# Charlieplex84.net
KiCad netlist of a schematic drawn in EAGLE
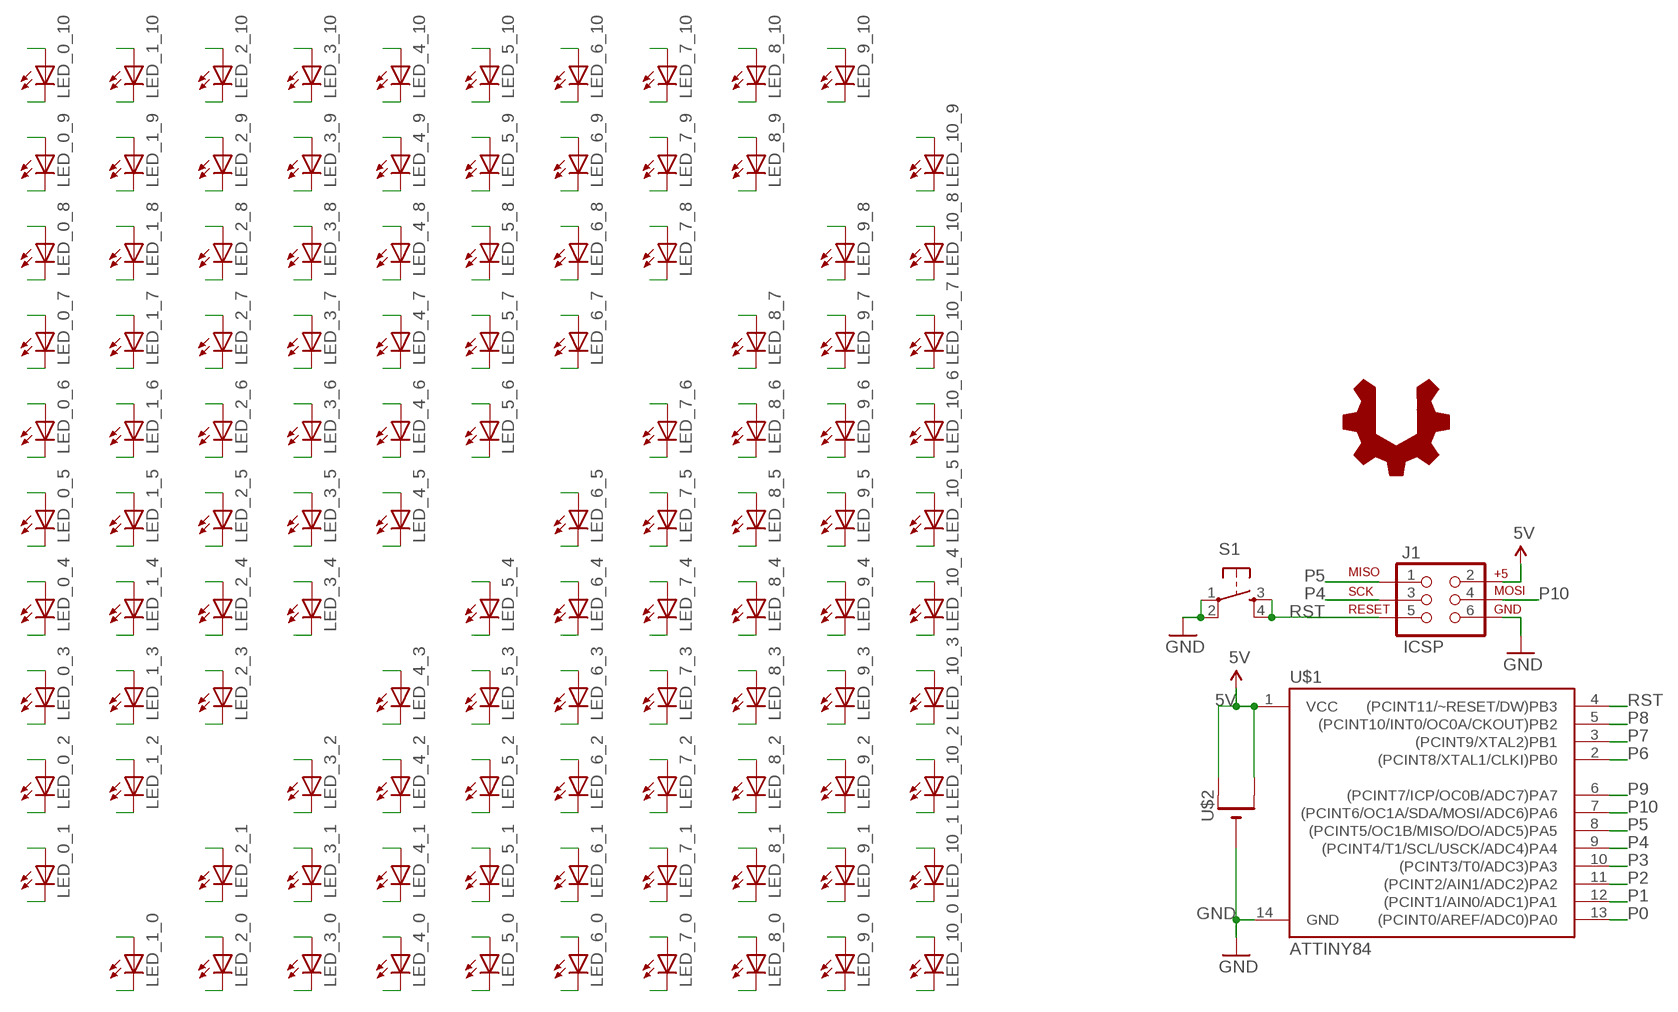
[diagram p0: schematic, sheet 1]

(export (version "E")
  (design (tool "Eeschema 10.0.6"))
  (components
    (comp (ref "J1")
      (value "ICSP")
      (footprint "eagle-import:2X3-NS")
      (libsource (lib "eagle-import") (part "AVR_SPI_PRG_6LABELED"))
    )
    (comp (ref "LED_0_1")
      (value "LEDOVAL")
      (footprint "eagle-import:LED-OVAL")
      (libsource (lib "eagle-import") (part "LEDOVAL"))
    )
    (comp (ref "LED_0_2")
      (value "LEDOVAL")
      (footprint "eagle-import:LED-OVAL")
      (libsource (lib "eagle-import") (part "LEDOVAL"))
    )
    (comp (ref "LED_0_3")
      (value "LEDOVAL")
      (footprint "eagle-import:LED-OVAL")
      (libsource (lib "eagle-import") (part "LEDOVAL"))
    )
    (comp (ref "LED_0_4")
      (value "LEDOVAL")
      (footprint "eagle-import:LED-OVAL")
      (libsource (lib "eagle-import") (part "LEDOVAL"))
    )
    (comp (ref "LED_0_5")
      (value "LEDOVAL")
      (footprint "eagle-import:LED-OVAL")
      (libsource (lib "eagle-import") (part "LEDOVAL"))
    )
    (comp (ref "LED_0_6")
      (value "LEDOVAL")
      (footprint "eagle-import:LED-OVAL")
      (libsource (lib "eagle-import") (part "LEDOVAL"))
    )
    (comp (ref "LED_0_7")
      (value "LEDOVAL")
      (footprint "eagle-import:LED-OVAL")
      (libsource (lib "eagle-import") (part "LEDOVAL"))
    )
    (comp (ref "LED_0_8")
      (value "LEDOVAL")
      (footprint "eagle-import:LED-OVAL")
      (libsource (lib "eagle-import") (part "LEDOVAL"))
    )
    (comp (ref "LED_0_9")
      (value "LEDOVAL")
      (footprint "eagle-import:LED-OVAL")
      (libsource (lib "eagle-import") (part "LEDOVAL"))
    )
    (comp (ref "LED_0_10")
      (value "LEDOVAL")
      (footprint "eagle-import:LED-OVAL")
      (libsource (lib "eagle-import") (part "LEDOVAL"))
    )
    (comp (ref "LED_1_0")
      (value "LEDOVAL")
      (footprint "eagle-import:LED-OVAL")
      (libsource (lib "eagle-import") (part "LEDOVAL"))
    )
    (comp (ref "LED_1_2")
      (value "LEDOVAL")
      (footprint "eagle-import:LED-OVAL")
      (libsource (lib "eagle-import") (part "LEDOVAL"))
    )
    (comp (ref "LED_1_3")
      (value "LEDOVAL")
      (footprint "eagle-import:LED-OVAL")
      (libsource (lib "eagle-import") (part "LEDOVAL"))
    )
    (comp (ref "LED_1_4")
      (value "LEDOVAL")
      (footprint "eagle-import:LED-OVAL")
      (libsource (lib "eagle-import") (part "LEDOVAL"))
    )
    (comp (ref "LED_1_5")
      (value "LEDOVAL")
      (footprint "eagle-import:LED-OVAL")
      (libsource (lib "eagle-import") (part "LEDOVAL"))
    )
    (comp (ref "LED_1_6")
      (value "LEDOVAL")
      (footprint "eagle-import:LED-OVAL")
      (libsource (lib "eagle-import") (part "LEDOVAL"))
    )
    (comp (ref "LED_1_7")
      (value "LEDOVAL")
      (footprint "eagle-import:LED-OVAL")
      (libsource (lib "eagle-import") (part "LEDOVAL"))
    )
    (comp (ref "LED_1_8")
      (value "LEDOVAL")
      (footprint "eagle-import:LED-OVAL")
      (libsource (lib "eagle-import") (part "LEDOVAL"))
    )
    (comp (ref "LED_1_9")
      (value "LEDOVAL")
      (footprint "eagle-import:LED-OVAL")
      (libsource (lib "eagle-import") (part "LEDOVAL"))
    )
    (comp (ref "LED_1_10")
      (value "LEDOVAL")
      (footprint "eagle-import:LED-OVAL")
      (libsource (lib "eagle-import") (part "LEDOVAL"))
    )
    (comp (ref "LED_2_0")
      (value "LEDOVAL")
      (footprint "eagle-import:LED-OVAL")
      (libsource (lib "eagle-import") (part "LEDOVAL"))
    )
    (comp (ref "LED_2_1")
      (value "LEDOVAL")
      (footprint "eagle-import:LED-OVAL")
      (libsource (lib "eagle-import") (part "LEDOVAL"))
    )
    (comp (ref "LED_2_3")
      (value "LEDOVAL")
      (footprint "eagle-import:LED-OVAL")
      (libsource (lib "eagle-import") (part "LEDOVAL"))
    )
    (comp (ref "LED_2_4")
      (value "LEDOVAL")
      (footprint "eagle-import:LED-OVAL")
      (libsource (lib "eagle-import") (part "LEDOVAL"))
    )
    (comp (ref "LED_2_5")
      (value "LEDOVAL")
      (footprint "eagle-import:LED-OVAL")
      (libsource (lib "eagle-import") (part "LEDOVAL"))
    )
    (comp (ref "LED_2_6")
      (value "LEDOVAL")
      (footprint "eagle-import:LED-OVAL")
      (libsource (lib "eagle-import") (part "LEDOVAL"))
    )
    (comp (ref "LED_2_7")
      (value "LEDOVAL")
      (footprint "eagle-import:LED-OVAL")
      (libsource (lib "eagle-import") (part "LEDOVAL"))
    )
    (comp (ref "LED_2_8")
      (value "LEDOVAL")
      (footprint "eagle-import:LED-OVAL")
      (libsource (lib "eagle-import") (part "LEDOVAL"))
    )
    (comp (ref "LED_2_9")
      (value "LEDOVAL")
      (footprint "eagle-import:LED-OVAL")
      (libsource (lib "eagle-import") (part "LEDOVAL"))
    )
    (comp (ref "LED_2_10")
      (value "LEDOVAL")
      (footprint "eagle-import:LED-OVAL")
      (libsource (lib "eagle-import") (part "LEDOVAL"))
    )
    (comp (ref "LED_3_0")
      (value "LEDOVAL")
      (footprint "eagle-import:LED-OVAL")
      (libsource (lib "eagle-import") (part "LEDOVAL"))
    )
    (comp (ref "LED_3_1")
      (value "LEDOVAL")
      (footprint "eagle-import:LED-OVAL")
      (libsource (lib "eagle-import") (part "LEDOVAL"))
    )
    (comp (ref "LED_3_2")
      (value "LEDOVAL")
      (footprint "eagle-import:LED-OVAL")
      (libsource (lib "eagle-import") (part "LEDOVAL"))
    )
    (comp (ref "LED_3_4")
      (value "LEDOVAL")
      (footprint "eagle-import:LED-OVAL")
      (libsource (lib "eagle-import") (part "LEDOVAL"))
    )
    (comp (ref "LED_3_5")
      (value "LEDOVAL")
      (footprint "eagle-import:LED-OVAL")
      (libsource (lib "eagle-import") (part "LEDOVAL"))
    )
    (comp (ref "LED_3_6")
      (value "LEDOVAL")
      (footprint "eagle-import:LED-OVAL")
      (libsource (lib "eagle-import") (part "LEDOVAL"))
    )
    (comp (ref "LED_3_7")
      (value "LEDOVAL")
      (footprint "eagle-import:LED-OVAL")
      (libsource (lib "eagle-import") (part "LEDOVAL"))
    )
    (comp (ref "LED_3_8")
      (value "LEDOVAL")
      (footprint "eagle-import:LED-OVAL")
      (libsource (lib "eagle-import") (part "LEDOVAL"))
    )
    (comp (ref "LED_3_9")
      (value "LEDOVAL")
      (footprint "eagle-import:LED-OVAL")
      (libsource (lib "eagle-import") (part "LEDOVAL"))
    )
    (comp (ref "LED_3_10")
      (value "LEDOVAL")
      (footprint "eagle-import:LED-OVAL")
      (libsource (lib "eagle-import") (part "LEDOVAL"))
    )
    (comp (ref "LED_4_0")
      (value "LEDOVAL")
      (footprint "eagle-import:LED-OVAL")
      (libsource (lib "eagle-import") (part "LEDOVAL"))
    )
    (comp (ref "LED_4_1")
      (value "LEDOVAL")
      (footprint "eagle-import:LED-OVAL")
      (libsource (lib "eagle-import") (part "LEDOVAL"))
    )
    (comp (ref "LED_4_2")
      (value "LEDOVAL")
      (footprint "eagle-import:LED-OVAL")
      (libsource (lib "eagle-import") (part "LEDOVAL"))
    )
    (comp (ref "LED_4_3")
      (value "LEDOVAL")
      (footprint "eagle-import:LED-OVAL")
      (libsource (lib "eagle-import") (part "LEDOVAL"))
    )
    (comp (ref "LED_4_5")
      (value "LEDOVAL")
      (footprint "eagle-import:LED-OVAL")
      (libsource (lib "eagle-import") (part "LEDOVAL"))
    )
    (comp (ref "LED_4_6")
      (value "LEDOVAL")
      (footprint "eagle-import:LED-OVAL")
      (libsource (lib "eagle-import") (part "LEDOVAL"))
    )
    (comp (ref "LED_4_7")
      (value "LEDOVAL")
      (footprint "eagle-import:LED-OVAL")
      (libsource (lib "eagle-import") (part "LEDOVAL"))
    )
    (comp (ref "LED_4_8")
      (value "LEDOVAL")
      (footprint "eagle-import:LED-OVAL")
      (libsource (lib "eagle-import") (part "LEDOVAL"))
    )
    (comp (ref "LED_4_9")
      (value "LEDOVAL")
      (footprint "eagle-import:LED-OVAL")
      (libsource (lib "eagle-import") (part "LEDOVAL"))
    )
    (comp (ref "LED_4_10")
      (value "LEDOVAL")
      (footprint "eagle-import:LED-OVAL")
      (libsource (lib "eagle-import") (part "LEDOVAL"))
    )
    (comp (ref "LED_5_0")
      (value "LEDOVAL")
      (footprint "eagle-import:LED-OVAL")
      (libsource (lib "eagle-import") (part "LEDOVAL"))
    )
    (comp (ref "LED_5_1")
      (value "LEDOVAL")
      (footprint "eagle-import:LED-OVAL")
      (libsource (lib "eagle-import") (part "LEDOVAL"))
    )
    (comp (ref "LED_5_2")
      (value "LEDOVAL")
      (footprint "eagle-import:LED-OVAL")
      (libsource (lib "eagle-import") (part "LEDOVAL"))
    )
    (comp (ref "LED_5_3")
      (value "LEDOVAL")
      (footprint "eagle-import:LED-OVAL")
      (libsource (lib "eagle-import") (part "LEDOVAL"))
    )
    (comp (ref "LED_5_4")
      (value "LEDOVAL")
      (footprint "eagle-import:LED-OVAL")
      (libsource (lib "eagle-import") (part "LEDOVAL"))
    )
    (comp (ref "LED_5_6")
      (value "LEDOVAL")
      (footprint "eagle-import:LED-OVAL")
      (libsource (lib "eagle-import") (part "LEDOVAL"))
    )
    (comp (ref "LED_5_7")
      (value "LEDOVAL")
      (footprint "eagle-import:LED-OVAL")
      (libsource (lib "eagle-import") (part "LEDOVAL"))
    )
    (comp (ref "LED_5_8")
      (value "LEDOVAL")
      (footprint "eagle-import:LED-OVAL")
      (libsource (lib "eagle-import") (part "LEDOVAL"))
    )
    (comp (ref "LED_5_9")
      (value "LEDOVAL")
      (footprint "eagle-import:LED-OVAL")
      (libsource (lib "eagle-import") (part "LEDOVAL"))
    )
    (comp (ref "LED_5_10")
      (value "LEDOVAL")
      (footprint "eagle-import:LED-OVAL")
      (libsource (lib "eagle-import") (part "LEDOVAL"))
    )
    (comp (ref "LED_6_0")
      (value "LEDOVAL")
      (footprint "eagle-import:LED-OVAL")
      (libsource (lib "eagle-import") (part "LEDOVAL"))
    )
    (comp (ref "LED_6_1")
      (value "LEDOVAL")
      (footprint "eagle-import:LED-OVAL")
      (libsource (lib "eagle-import") (part "LEDOVAL"))
    )
    (comp (ref "LED_6_2")
      (value "LEDOVAL")
      (footprint "eagle-import:LED-OVAL")
      (libsource (lib "eagle-import") (part "LEDOVAL"))
    )
    (comp (ref "LED_6_3")
      (value "LEDOVAL")
      (footprint "eagle-import:LED-OVAL")
      (libsource (lib "eagle-import") (part "LEDOVAL"))
    )
    (comp (ref "LED_6_4")
      (value "LEDOVAL")
      (footprint "eagle-import:LED-OVAL")
      (libsource (lib "eagle-import") (part "LEDOVAL"))
    )
    (comp (ref "LED_6_5")
      (value "LEDOVAL")
      (footprint "eagle-import:LED-OVAL")
      (libsource (lib "eagle-import") (part "LEDOVAL"))
    )
    (comp (ref "LED_6_7")
      (value "LEDOVAL")
      (footprint "eagle-import:LED-OVAL")
      (libsource (lib "eagle-import") (part "LEDOVAL"))
    )
    (comp (ref "LED_6_8")
      (value "LEDOVAL")
      (footprint "eagle-import:LED-OVAL")
      (libsource (lib "eagle-import") (part "LEDOVAL"))
    )
    (comp (ref "LED_6_9")
      (value "LEDOVAL")
      (footprint "eagle-import:LED-OVAL")
      (libsource (lib "eagle-import") (part "LEDOVAL"))
    )
    (comp (ref "LED_6_10")
      (value "LEDOVAL")
      (footprint "eagle-import:LED-OVAL")
      (libsource (lib "eagle-import") (part "LEDOVAL"))
    )
    (comp (ref "LED_7_0")
      (value "LEDOVAL")
      (footprint "eagle-import:LED-OVAL")
      (libsource (lib "eagle-import") (part "LEDOVAL"))
    )
    (comp (ref "LED_7_1")
      (value "LEDOVAL")
      (footprint "eagle-import:LED-OVAL")
      (libsource (lib "eagle-import") (part "LEDOVAL"))
    )
    (comp (ref "LED_7_2")
      (value "LEDOVAL")
      (footprint "eagle-import:LED-OVAL")
      (libsource (lib "eagle-import") (part "LEDOVAL"))
    )
    (comp (ref "LED_7_3")
      (value "LEDOVAL")
      (footprint "eagle-import:LED-OVAL")
      (libsource (lib "eagle-import") (part "LEDOVAL"))
    )
    (comp (ref "LED_7_4")
      (value "LEDOVAL")
      (footprint "eagle-import:LED-OVAL")
      (libsource (lib "eagle-import") (part "LEDOVAL"))
    )
    (comp (ref "LED_7_5")
      (value "LEDOVAL")
      (footprint "eagle-import:LED-OVAL")
      (libsource (lib "eagle-import") (part "LEDOVAL"))
    )
    (comp (ref "LED_7_6")
      (value "LEDOVAL")
      (footprint "eagle-import:LED-OVAL")
      (libsource (lib "eagle-import") (part "LEDOVAL"))
    )
    (comp (ref "LED_7_8")
      (value "LEDOVAL")
      (footprint "eagle-import:LED-OVAL")
      (libsource (lib "eagle-import") (part "LEDOVAL"))
    )
    (comp (ref "LED_7_9")
      (value "LEDOVAL")
      (footprint "eagle-import:LED-OVAL")
      (libsource (lib "eagle-import") (part "LEDOVAL"))
    )
    (comp (ref "LED_7_10")
      (value "LEDOVAL")
      (footprint "eagle-import:LED-OVAL")
      (libsource (lib "eagle-import") (part "LEDOVAL"))
    )
    (comp (ref "LED_8_0")
      (value "LEDOVAL")
      (footprint "eagle-import:LED-OVAL")
      (libsource (lib "eagle-import") (part "LEDOVAL"))
    )
    (comp (ref "LED_8_1")
      (value "LEDOVAL")
      (footprint "eagle-import:LED-OVAL")
      (libsource (lib "eagle-import") (part "LEDOVAL"))
    )
    (comp (ref "LED_8_2")
      (value "LEDOVAL")
      (footprint "eagle-import:LED-OVAL")
      (libsource (lib "eagle-import") (part "LEDOVAL"))
    )
    (comp (ref "LED_8_3")
      (value "LEDOVAL")
      (footprint "eagle-import:LED-OVAL")
      (libsource (lib "eagle-import") (part "LEDOVAL"))
    )
    (comp (ref "LED_8_4")
      (value "LEDOVAL")
      (footprint "eagle-import:LED-OVAL")
      (libsource (lib "eagle-import") (part "LEDOVAL"))
    )
    (comp (ref "LED_8_5")
      (value "LEDOVAL")
      (footprint "eagle-import:LED-OVAL")
      (libsource (lib "eagle-import") (part "LEDOVAL"))
    )
    (comp (ref "LED_8_6")
      (value "LEDOVAL")
      (footprint "eagle-import:LED-OVAL")
      (libsource (lib "eagle-import") (part "LEDOVAL"))
    )
    (comp (ref "LED_8_7")
      (value "LEDOVAL")
      (footprint "eagle-import:LED-OVAL")
      (libsource (lib "eagle-import") (part "LEDOVAL"))
    )
    (comp (ref "LED_8_9")
      (value "LEDOVAL")
      (footprint "eagle-import:LED-OVAL")
      (libsource (lib "eagle-import") (part "LEDOVAL"))
    )
    (comp (ref "LED_8_10")
      (value "LEDOVAL")
      (footprint "eagle-import:LED-OVAL")
      (libsource (lib "eagle-import") (part "LEDOVAL"))
    )
    (comp (ref "LED_9_0")
      (value "LEDOVAL")
      (footprint "eagle-import:LED-OVAL")
      (libsource (lib "eagle-import") (part "LEDOVAL"))
    )
    (comp (ref "LED_9_1")
      (value "LEDOVAL")
      (footprint "eagle-import:LED-OVAL")
      (libsource (lib "eagle-import") (part "LEDOVAL"))
    )
    (comp (ref "LED_9_2")
      (value "LEDOVAL")
      (footprint "eagle-import:LED-OVAL")
      (libsource (lib "eagle-import") (part "LEDOVAL"))
    )
    (comp (ref "LED_9_3")
      (value "LEDOVAL")
      (footprint "eagle-import:LED-OVAL")
      (libsource (lib "eagle-import") (part "LEDOVAL"))
    )
    (comp (ref "LED_9_4")
      (value "LEDOVAL")
      (footprint "eagle-import:LED-OVAL")
      (libsource (lib "eagle-import") (part "LEDOVAL"))
    )
    (comp (ref "LED_9_5")
      (value "LEDOVAL")
      (footprint "eagle-import:LED-OVAL")
      (libsource (lib "eagle-import") (part "LEDOVAL"))
    )
    (comp (ref "LED_9_6")
      (value "LEDOVAL")
      (footprint "eagle-import:LED-OVAL")
      (libsource (lib "eagle-import") (part "LEDOVAL"))
    )
    (comp (ref "LED_9_7")
      (value "LEDOVAL")
      (footprint "eagle-import:LED-OVAL")
      (libsource (lib "eagle-import") (part "LEDOVAL"))
    )
    (comp (ref "LED_9_8")
      (value "LEDOVAL")
      (footprint "eagle-import:LED-OVAL")
      (libsource (lib "eagle-import") (part "LEDOVAL"))
    )
    (comp (ref "LED_9_10")
      (value "LEDOVAL")
      (footprint "eagle-import:LED-OVAL")
      (libsource (lib "eagle-import") (part "LEDOVAL"))
    )
    (comp (ref "LED_10_0")
      (value "LEDOVAL")
      (footprint "eagle-import:LED-OVAL")
      (libsource (lib "eagle-import") (part "LEDOVAL"))
    )
    (comp (ref "LED_10_1")
      (value "LEDOVAL")
      (footprint "eagle-import:LED-OVAL")
      (libsource (lib "eagle-import") (part "LEDOVAL"))
    )
    (comp (ref "LED_10_2")
      (value "LEDOVAL")
      (footprint "eagle-import:LED-OVAL")
      (libsource (lib "eagle-import") (part "LEDOVAL"))
    )
    (comp (ref "LED_10_3")
      (value "LEDOVAL")
      (footprint "eagle-import:LED-OVAL")
      (libsource (lib "eagle-import") (part "LEDOVAL"))
    )
    (comp (ref "LED_10_4")
      (value "LEDOVAL")
      (footprint "eagle-import:LED-OVAL")
      (libsource (lib "eagle-import") (part "LEDOVAL"))
    )
    (comp (ref "LED_10_5")
      (value "LEDOVAL")
      (footprint "eagle-import:LED-OVAL")
      (libsource (lib "eagle-import") (part "LEDOVAL"))
    )
    (comp (ref "LED_10_6")
      (value "LEDOVAL")
      (footprint "eagle-import:LED-OVAL")
      (libsource (lib "eagle-import") (part "LEDOVAL"))
    )
    (comp (ref "LED_10_7")
      (value "LEDOVAL")
      (footprint "eagle-import:LED-OVAL")
      (libsource (lib "eagle-import") (part "LEDOVAL"))
    )
    (comp (ref "LED_10_8")
      (value "LEDOVAL")
      (footprint "eagle-import:LED-OVAL")
      (libsource (lib "eagle-import") (part "LEDOVAL"))
    )
    (comp (ref "LED_10_9")
      (value "LEDOVAL")
      (footprint "eagle-import:LED-OVAL")
      (libsource (lib "eagle-import") (part "LEDOVAL"))
    )
    (comp (ref "S1")
      (value "TAC_SWITCHPTH")
      (footprint "eagle-import:TACTILE-PTH")
      (libsource (lib "eagle-import") (part "TAC_SWITCHPTH"))
    )
    (comp (ref "U$1")
      (value "ATTINY84")
      (footprint "eagle-import:DIL14")
      (libsource (lib "eagle-import") (part "ATTINY84ATTINY84-20PU"))
    )
    (comp (ref "U$2")
      (value "CR2032THM")
      (footprint "eagle-import:CR2032-THRU")
      (libsource (lib "eagle-import") (part "CR2032THM"))
    )
    (comp (ref "U$3")
      (value "USER_HACKABLE")
      (footprint "eagle-import:USER_HACKABLE")
      (libsource (lib "eagle-import") (part "USER_HACKABLE"))
    )
  )
  (nets
    (net (code "1") (name "/P0") (class "Default")
      (node (ref "LED_0_1") (pin "CATHODE") (pinfunction "C_CATHODE") (pintype "passive"))
      (node (ref "LED_0_10") (pin "CATHODE") (pinfunction "C_CATHODE") (pintype "passive"))
      (node (ref "LED_0_2") (pin "CATHODE") (pinfunction "C_CATHODE") (pintype "passive"))
      (node (ref "LED_0_3") (pin "CATHODE") (pinfunction "C_CATHODE") (pintype "passive"))
      (node (ref "LED_0_4") (pin "CATHODE") (pinfunction "C_CATHODE") (pintype "passive"))
      (node (ref "LED_0_5") (pin "CATHODE") (pinfunction "C_CATHODE") (pintype "passive"))
      (node (ref "LED_0_6") (pin "CATHODE") (pinfunction "C_CATHODE") (pintype "passive"))
      (node (ref "LED_0_7") (pin "CATHODE") (pinfunction "C_CATHODE") (pintype "passive"))
      (node (ref "LED_0_8") (pin "CATHODE") (pinfunction "C_CATHODE") (pintype "passive"))
      (node (ref "LED_0_9") (pin "CATHODE") (pinfunction "C_CATHODE") (pintype "passive"))
      (node (ref "LED_10_0") (pin "ANODE") (pinfunction "A_ANODE") (pintype "passive"))
      (node (ref "LED_1_0") (pin "ANODE") (pinfunction "A_ANODE") (pintype "passive"))
      (node (ref "LED_2_0") (pin "ANODE") (pinfunction "A_ANODE") (pintype "passive"))
      (node (ref "LED_3_0") (pin "ANODE") (pinfunction "A_ANODE") (pintype "passive"))
      (node (ref "LED_4_0") (pin "ANODE") (pinfunction "A_ANODE") (pintype "passive"))
      (node (ref "LED_5_0") (pin "ANODE") (pinfunction "A_ANODE") (pintype "passive"))
      (node (ref "LED_6_0") (pin "ANODE") (pinfunction "A_ANODE") (pintype "passive"))
      (node (ref "LED_7_0") (pin "ANODE") (pinfunction "A_ANODE") (pintype "passive"))
      (node (ref "LED_8_0") (pin "ANODE") (pinfunction "A_ANODE") (pintype "passive"))
      (node (ref "LED_9_0") (pin "ANODE") (pinfunction "A_ANODE") (pintype "passive"))
      (node (ref "U$1") (pin "13") (pinfunction "(PCINT0/AREF/ADC0)PA0_13") (pintype "bidirectional"))
    )
    (net (code "2") (name "/P1") (class "Default")
      (node (ref "LED_0_1") (pin "ANODE") (pinfunction "A_ANODE") (pintype "passive"))
      (node (ref "LED_10_1") (pin "ANODE") (pinfunction "A_ANODE") (pintype "passive"))
      (node (ref "LED_1_0") (pin "CATHODE") (pinfunction "C_CATHODE") (pintype "passive"))
      (node (ref "LED_1_10") (pin "CATHODE") (pinfunction "C_CATHODE") (pintype "passive"))
      (node (ref "LED_1_2") (pin "CATHODE") (pinfunction "C_CATHODE") (pintype "passive"))
      (node (ref "LED_1_3") (pin "CATHODE") (pinfunction "C_CATHODE") (pintype "passive"))
      (node (ref "LED_1_4") (pin "CATHODE") (pinfunction "C_CATHODE") (pintype "passive"))
      (node (ref "LED_1_5") (pin "CATHODE") (pinfunction "C_CATHODE") (pintype "passive"))
      (node (ref "LED_1_6") (pin "CATHODE") (pinfunction "C_CATHODE") (pintype "passive"))
      (node (ref "LED_1_7") (pin "CATHODE") (pinfunction "C_CATHODE") (pintype "passive"))
      (node (ref "LED_1_8") (pin "CATHODE") (pinfunction "C_CATHODE") (pintype "passive"))
      (node (ref "LED_1_9") (pin "CATHODE") (pinfunction "C_CATHODE") (pintype "passive"))
      (node (ref "LED_2_1") (pin "ANODE") (pinfunction "A_ANODE") (pintype "passive"))
      (node (ref "LED_3_1") (pin "ANODE") (pinfunction "A_ANODE") (pintype "passive"))
      (node (ref "LED_4_1") (pin "ANODE") (pinfunction "A_ANODE") (pintype "passive"))
      (node (ref "LED_5_1") (pin "ANODE") (pinfunction "A_ANODE") (pintype "passive"))
      (node (ref "LED_6_1") (pin "ANODE") (pinfunction "A_ANODE") (pintype "passive"))
      (node (ref "LED_7_1") (pin "ANODE") (pinfunction "A_ANODE") (pintype "passive"))
      (node (ref "LED_8_1") (pin "ANODE") (pinfunction "A_ANODE") (pintype "passive"))
      (node (ref "LED_9_1") (pin "ANODE") (pinfunction "A_ANODE") (pintype "passive"))
      (node (ref "U$1") (pin "12") (pinfunction "(PCINT1/AIN0/ADC1)PA1_12") (pintype "bidirectional"))
    )
    (net (code "3") (name "/P2") (class "Default")
      (node (ref "LED_0_2") (pin "ANODE") (pinfunction "A_ANODE") (pintype "passive"))
      (node (ref "LED_10_2") (pin "ANODE") (pinfunction "A_ANODE") (pintype "passive"))
      (node (ref "LED_1_2") (pin "ANODE") (pinfunction "A_ANODE") (pintype "passive"))
      (node (ref "LED_2_0") (pin "CATHODE") (pinfunction "C_CATHODE") (pintype "passive"))
      (node (ref "LED_2_1") (pin "CATHODE") (pinfunction "C_CATHODE") (pintype "passive"))
      (node (ref "LED_2_10") (pin "CATHODE") (pinfunction "C_CATHODE") (pintype "passive"))
      (node (ref "LED_2_3") (pin "CATHODE") (pinfunction "C_CATHODE") (pintype "passive"))
      (node (ref "LED_2_4") (pin "CATHODE") (pinfunction "C_CATHODE") (pintype "passive"))
      (node (ref "LED_2_5") (pin "CATHODE") (pinfunction "C_CATHODE") (pintype "passive"))
      (node (ref "LED_2_6") (pin "CATHODE") (pinfunction "C_CATHODE") (pintype "passive"))
      (node (ref "LED_2_7") (pin "CATHODE") (pinfunction "C_CATHODE") (pintype "passive"))
      (node (ref "LED_2_8") (pin "CATHODE") (pinfunction "C_CATHODE") (pintype "passive"))
      (node (ref "LED_2_9") (pin "CATHODE") (pinfunction "C_CATHODE") (pintype "passive"))
      (node (ref "LED_3_2") (pin "ANODE") (pinfunction "A_ANODE") (pintype "passive"))
      (node (ref "LED_4_2") (pin "ANODE") (pinfunction "A_ANODE") (pintype "passive"))
      (node (ref "LED_5_2") (pin "ANODE") (pinfunction "A_ANODE") (pintype "passive"))
      (node (ref "LED_6_2") (pin "ANODE") (pinfunction "A_ANODE") (pintype "passive"))
      (node (ref "LED_7_2") (pin "ANODE") (pinfunction "A_ANODE") (pintype "passive"))
      (node (ref "LED_8_2") (pin "ANODE") (pinfunction "A_ANODE") (pintype "passive"))
      (node (ref "LED_9_2") (pin "ANODE") (pinfunction "A_ANODE") (pintype "passive"))
      (node (ref "U$1") (pin "11") (pinfunction "(PCINT2/AIN1/ADC2)PA2_11") (pintype "bidirectional"))
    )
    (net (code "4") (name "/P3") (class "Default")
      (node (ref "LED_0_3") (pin "ANODE") (pinfunction "A_ANODE") (pintype "passive"))
      (node (ref "LED_10_3") (pin "ANODE") (pinfunction "A_ANODE") (pintype "passive"))
      (node (ref "LED_1_3") (pin "ANODE") (pinfunction "A_ANODE") (pintype "passive"))
      (node (ref "LED_2_3") (pin "ANODE") (pinfunction "A_ANODE") (pintype "passive"))
      (node (ref "LED_3_0") (pin "CATHODE") (pinfunction "C_CATHODE") (pintype "passive"))
      (node (ref "LED_3_1") (pin "CATHODE") (pinfunction "C_CATHODE") (pintype "passive"))
      (node (ref "LED_3_10") (pin "CATHODE") (pinfunction "C_CATHODE") (pintype "passive"))
      (node (ref "LED_3_2") (pin "CATHODE") (pinfunction "C_CATHODE") (pintype "passive"))
      (node (ref "LED_3_4") (pin "CATHODE") (pinfunction "C_CATHODE") (pintype "passive"))
      (node (ref "LED_3_5") (pin "CATHODE") (pinfunction "C_CATHODE") (pintype "passive"))
      (node (ref "LED_3_6") (pin "CATHODE") (pinfunction "C_CATHODE") (pintype "passive"))
      (node (ref "LED_3_7") (pin "CATHODE") (pinfunction "C_CATHODE") (pintype "passive"))
      (node (ref "LED_3_8") (pin "CATHODE") (pinfunction "C_CATHODE") (pintype "passive"))
      (node (ref "LED_3_9") (pin "CATHODE") (pinfunction "C_CATHODE") (pintype "passive"))
      (node (ref "LED_4_3") (pin "ANODE") (pinfunction "A_ANODE") (pintype "passive"))
      (node (ref "LED_5_3") (pin "ANODE") (pinfunction "A_ANODE") (pintype "passive"))
      (node (ref "LED_6_3") (pin "ANODE") (pinfunction "A_ANODE") (pintype "passive"))
      (node (ref "LED_7_3") (pin "ANODE") (pinfunction "A_ANODE") (pintype "passive"))
      (node (ref "LED_8_3") (pin "ANODE") (pinfunction "A_ANODE") (pintype "passive"))
      (node (ref "LED_9_3") (pin "ANODE") (pinfunction "A_ANODE") (pintype "passive"))
      (node (ref "U$1") (pin "10") (pinfunction "(PCINT3/T0/ADC3)PA3_10") (pintype "bidirectional"))
    )
    (net (code "5") (name "/P4") (class "Default")
      (node (ref "J1") (pin "3") (pinfunction "3_3") (pintype "passive"))
      (node (ref "LED_0_4") (pin "ANODE") (pinfunction "A_ANODE") (pintype "passive"))
      (node (ref "LED_10_4") (pin "ANODE") (pinfunction "A_ANODE") (pintype "passive"))
      (node (ref "LED_1_4") (pin "ANODE") (pinfunction "A_ANODE") (pintype "passive"))
      (node (ref "LED_2_4") (pin "ANODE") (pinfunction "A_ANODE") (pintype "passive"))
      (node (ref "LED_3_4") (pin "ANODE") (pinfunction "A_ANODE") (pintype "passive"))
      (node (ref "LED_4_0") (pin "CATHODE") (pinfunction "C_CATHODE") (pintype "passive"))
      (node (ref "LED_4_1") (pin "CATHODE") (pinfunction "C_CATHODE") (pintype "passive"))
      (node (ref "LED_4_10") (pin "CATHODE") (pinfunction "C_CATHODE") (pintype "passive"))
      (node (ref "LED_4_2") (pin "CATHODE") (pinfunction "C_CATHODE") (pintype "passive"))
      (node (ref "LED_4_3") (pin "CATHODE") (pinfunction "C_CATHODE") (pintype "passive"))
      (node (ref "LED_4_5") (pin "CATHODE") (pinfunction "C_CATHODE") (pintype "passive"))
      (node (ref "LED_4_6") (pin "CATHODE") (pinfunction "C_CATHODE") (pintype "passive"))
      (node (ref "LED_4_7") (pin "CATHODE") (pinfunction "C_CATHODE") (pintype "passive"))
      (node (ref "LED_4_8") (pin "CATHODE") (pinfunction "C_CATHODE") (pintype "passive"))
      (node (ref "LED_4_9") (pin "CATHODE") (pinfunction "C_CATHODE") (pintype "passive"))
      (node (ref "LED_5_4") (pin "ANODE") (pinfunction "A_ANODE") (pintype "passive"))
      (node (ref "LED_6_4") (pin "ANODE") (pinfunction "A_ANODE") (pintype "passive"))
      (node (ref "LED_7_4") (pin "ANODE") (pinfunction "A_ANODE") (pintype "passive"))
      (node (ref "LED_8_4") (pin "ANODE") (pinfunction "A_ANODE") (pintype "passive"))
      (node (ref "LED_9_4") (pin "ANODE") (pinfunction "A_ANODE") (pintype "passive"))
      (node (ref "U$1") (pin "9") (pinfunction "(PCINT4/T1/SCL/USCK/ADC4)PA4_9") (pintype "bidirectional"))
    )
    (net (code "6") (name "/P5") (class "Default")
      (node (ref "J1") (pin "1") (pinfunction "1_1") (pintype "passive"))
      (node (ref "LED_0_5") (pin "ANODE") (pinfunction "A_ANODE") (pintype "passive"))
      (node (ref "LED_10_5") (pin "ANODE") (pinfunction "A_ANODE") (pintype "passive"))
      (node (ref "LED_1_5") (pin "ANODE") (pinfunction "A_ANODE") (pintype "passive"))
      (node (ref "LED_2_5") (pin "ANODE") (pinfunction "A_ANODE") (pintype "passive"))
      (node (ref "LED_3_5") (pin "ANODE") (pinfunction "A_ANODE") (pintype "passive"))
      (node (ref "LED_4_5") (pin "ANODE") (pinfunction "A_ANODE") (pintype "passive"))
      (node (ref "LED_5_0") (pin "CATHODE") (pinfunction "C_CATHODE") (pintype "passive"))
      (node (ref "LED_5_1") (pin "CATHODE") (pinfunction "C_CATHODE") (pintype "passive"))
      (node (ref "LED_5_10") (pin "CATHODE") (pinfunction "C_CATHODE") (pintype "passive"))
      (node (ref "LED_5_2") (pin "CATHODE") (pinfunction "C_CATHODE") (pintype "passive"))
      (node (ref "LED_5_3") (pin "CATHODE") (pinfunction "C_CATHODE") (pintype "passive"))
      (node (ref "LED_5_4") (pin "CATHODE") (pinfunction "C_CATHODE") (pintype "passive"))
      (node (ref "LED_5_6") (pin "CATHODE") (pinfunction "C_CATHODE") (pintype "passive"))
      (node (ref "LED_5_7") (pin "CATHODE") (pinfunction "C_CATHODE") (pintype "passive"))
      (node (ref "LED_5_8") (pin "CATHODE") (pinfunction "C_CATHODE") (pintype "passive"))
      (node (ref "LED_5_9") (pin "CATHODE") (pinfunction "C_CATHODE") (pintype "passive"))
      (node (ref "LED_6_5") (pin "ANODE") (pinfunction "A_ANODE") (pintype "passive"))
      (node (ref "LED_7_5") (pin "ANODE") (pinfunction "A_ANODE") (pintype "passive"))
      (node (ref "LED_8_5") (pin "ANODE") (pinfunction "A_ANODE") (pintype "passive"))
      (node (ref "LED_9_5") (pin "ANODE") (pinfunction "A_ANODE") (pintype "passive"))
      (node (ref "U$1") (pin "8") (pinfunction "(PCINT5/OC1B/MISO/DO/ADC5)PA5_8") (pintype "bidirectional"))
    )
    (net (code "7") (name "/P6") (class "Default")
      (node (ref "LED_0_6") (pin "ANODE") (pinfunction "A_ANODE") (pintype "passive"))
      (node (ref "LED_10_6") (pin "ANODE") (pinfunction "A_ANODE") (pintype "passive"))
      (node (ref "LED_1_6") (pin "ANODE") (pinfunction "A_ANODE") (pintype "passive"))
      (node (ref "LED_2_6") (pin "ANODE") (pinfunction "A_ANODE") (pintype "passive"))
      (node (ref "LED_3_6") (pin "ANODE") (pinfunction "A_ANODE") (pintype "passive"))
      (node (ref "LED_4_6") (pin "ANODE") (pinfunction "A_ANODE") (pintype "passive"))
      (node (ref "LED_5_6") (pin "ANODE") (pinfunction "A_ANODE") (pintype "passive"))
      (node (ref "LED_6_0") (pin "CATHODE") (pinfunction "C_CATHODE") (pintype "passive"))
      (node (ref "LED_6_1") (pin "CATHODE") (pinfunction "C_CATHODE") (pintype "passive"))
      (node (ref "LED_6_10") (pin "CATHODE") (pinfunction "C_CATHODE") (pintype "passive"))
      (node (ref "LED_6_2") (pin "CATHODE") (pinfunction "C_CATHODE") (pintype "passive"))
      (node (ref "LED_6_3") (pin "CATHODE") (pinfunction "C_CATHODE") (pintype "passive"))
      (node (ref "LED_6_4") (pin "CATHODE") (pinfunction "C_CATHODE") (pintype "passive"))
      (node (ref "LED_6_5") (pin "CATHODE") (pinfunction "C_CATHODE") (pintype "passive"))
      (node (ref "LED_6_7") (pin "CATHODE") (pinfunction "C_CATHODE") (pintype "passive"))
      (node (ref "LED_6_8") (pin "CATHODE") (pinfunction "C_CATHODE") (pintype "passive"))
      (node (ref "LED_6_9") (pin "CATHODE") (pinfunction "C_CATHODE") (pintype "passive"))
      (node (ref "LED_7_6") (pin "ANODE") (pinfunction "A_ANODE") (pintype "passive"))
      (node (ref "LED_8_6") (pin "ANODE") (pinfunction "A_ANODE") (pintype "passive"))
      (node (ref "LED_9_6") (pin "ANODE") (pinfunction "A_ANODE") (pintype "passive"))
      (node (ref "U$1") (pin "2") (pinfunction "(PCINT8/XTAL1/CLKI)PB0_2") (pintype "bidirectional"))
    )
    (net (code "8") (name "/P7") (class "Default")
      (node (ref "LED_0_7") (pin "ANODE") (pinfunction "A_ANODE") (pintype "passive"))
      (node (ref "LED_10_7") (pin "ANODE") (pinfunction "A_ANODE") (pintype "passive"))
      (node (ref "LED_1_7") (pin "ANODE") (pinfunction "A_ANODE") (pintype "passive"))
      (node (ref "LED_2_7") (pin "ANODE") (pinfunction "A_ANODE") (pintype "passive"))
      (node (ref "LED_3_7") (pin "ANODE") (pinfunction "A_ANODE") (pintype "passive"))
      (node (ref "LED_4_7") (pin "ANODE") (pinfunction "A_ANODE") (pintype "passive"))
      (node (ref "LED_5_7") (pin "ANODE") (pinfunction "A_ANODE") (pintype "passive"))
      (node (ref "LED_6_7") (pin "ANODE") (pinfunction "A_ANODE") (pintype "passive"))
      (node (ref "LED_7_0") (pin "CATHODE") (pinfunction "C_CATHODE") (pintype "passive"))
      (node (ref "LED_7_1") (pin "CATHODE") (pinfunction "C_CATHODE") (pintype "passive"))
      (node (ref "LED_7_10") (pin "CATHODE") (pinfunction "C_CATHODE") (pintype "passive"))
      (node (ref "LED_7_2") (pin "CATHODE") (pinfunction "C_CATHODE") (pintype "passive"))
      (node (ref "LED_7_3") (pin "CATHODE") (pinfunction "C_CATHODE") (pintype "passive"))
      (node (ref "LED_7_4") (pin "CATHODE") (pinfunction "C_CATHODE") (pintype "passive"))
      (node (ref "LED_7_5") (pin "CATHODE") (pinfunction "C_CATHODE") (pintype "passive"))
      (node (ref "LED_7_6") (pin "CATHODE") (pinfunction "C_CATHODE") (pintype "passive"))
      (node (ref "LED_7_8") (pin "CATHODE") (pinfunction "C_CATHODE") (pintype "passive"))
      (node (ref "LED_7_9") (pin "CATHODE") (pinfunction "C_CATHODE") (pintype "passive"))
      (node (ref "LED_8_7") (pin "ANODE") (pinfunction "A_ANODE") (pintype "passive"))
      (node (ref "LED_9_7") (pin "ANODE") (pinfunction "A_ANODE") (pintype "passive"))
      (node (ref "U$1") (pin "3") (pinfunction "(PCINT9/XTAL2)PB1_3") (pintype "bidirectional"))
    )
    (net (code "9") (name "/P8") (class "Default")
      (node (ref "LED_0_8") (pin "ANODE") (pinfunction "A_ANODE") (pintype "passive"))
      (node (ref "LED_10_8") (pin "ANODE") (pinfunction "A_ANODE") (pintype "passive"))
      (node (ref "LED_1_8") (pin "ANODE") (pinfunction "A_ANODE") (pintype "passive"))
      (node (ref "LED_2_8") (pin "ANODE") (pinfunction "A_ANODE") (pintype "passive"))
      (node (ref "LED_3_8") (pin "ANODE") (pinfunction "A_ANODE") (pintype "passive"))
      (node (ref "LED_4_8") (pin "ANODE") (pinfunction "A_ANODE") (pintype "passive"))
      (node (ref "LED_5_8") (pin "ANODE") (pinfunction "A_ANODE") (pintype "passive"))
      (node (ref "LED_6_8") (pin "ANODE") (pinfunction "A_ANODE") (pintype "passive"))
      (node (ref "LED_7_8") (pin "ANODE") (pinfunction "A_ANODE") (pintype "passive"))
      (node (ref "LED_8_0") (pin "CATHODE") (pinfunction "C_CATHODE") (pintype "passive"))
      (node (ref "LED_8_1") (pin "CATHODE") (pinfunction "C_CATHODE") (pintype "passive"))
      (node (ref "LED_8_10") (pin "CATHODE") (pinfunction "C_CATHODE") (pintype "passive"))
      (node (ref "LED_8_2") (pin "CATHODE") (pinfunction "C_CATHODE") (pintype "passive"))
      (node (ref "LED_8_3") (pin "CATHODE") (pinfunction "C_CATHODE") (pintype "passive"))
      (node (ref "LED_8_4") (pin "CATHODE") (pinfunction "C_CATHODE") (pintype "passive"))
      (node (ref "LED_8_5") (pin "CATHODE") (pinfunction "C_CATHODE") (pintype "passive"))
      (node (ref "LED_8_6") (pin "CATHODE") (pinfunction "C_CATHODE") (pintype "passive"))
      (node (ref "LED_8_7") (pin "CATHODE") (pinfunction "C_CATHODE") (pintype "passive"))
      (node (ref "LED_8_9") (pin "CATHODE") (pinfunction "C_CATHODE") (pintype "passive"))
      (node (ref "LED_9_8") (pin "ANODE") (pinfunction "A_ANODE") (pintype "passive"))
      (node (ref "U$1") (pin "5") (pinfunction "(PCINT10/INT0/OC0A/CKOUT)PB2_5") (pintype "bidirectional"))
    )
    (net (code "10") (name "/P9") (class "Default")
      (node (ref "LED_0_9") (pin "ANODE") (pinfunction "A_ANODE") (pintype "passive"))
      (node (ref "LED_10_9") (pin "ANODE") (pinfunction "A_ANODE") (pintype "passive"))
      (node (ref "LED_1_9") (pin "ANODE") (pinfunction "A_ANODE") (pintype "passive"))
      (node (ref "LED_2_9") (pin "ANODE") (pinfunction "A_ANODE") (pintype "passive"))
      (node (ref "LED_3_9") (pin "ANODE") (pinfunction "A_ANODE") (pintype "passive"))
      (node (ref "LED_4_9") (pin "ANODE") (pinfunction "A_ANODE") (pintype "passive"))
      (node (ref "LED_5_9") (pin "ANODE") (pinfunction "A_ANODE") (pintype "passive"))
      (node (ref "LED_6_9") (pin "ANODE") (pinfunction "A_ANODE") (pintype "passive"))
      (node (ref "LED_7_9") (pin "ANODE") (pinfunction "A_ANODE") (pintype "passive"))
      (node (ref "LED_8_9") (pin "ANODE") (pinfunction "A_ANODE") (pintype "passive"))
      (node (ref "LED_9_0") (pin "CATHODE") (pinfunction "C_CATHODE") (pintype "passive"))
      (node (ref "LED_9_1") (pin "CATHODE") (pinfunction "C_CATHODE") (pintype "passive"))
      (node (ref "LED_9_10") (pin "CATHODE") (pinfunction "C_CATHODE") (pintype "passive"))
      (node (ref "LED_9_2") (pin "CATHODE") (pinfunction "C_CATHODE") (pintype "passive"))
      (node (ref "LED_9_3") (pin "CATHODE") (pinfunction "C_CATHODE") (pintype "passive"))
      (node (ref "LED_9_4") (pin "CATHODE") (pinfunction "C_CATHODE") (pintype "passive"))
      (node (ref "LED_9_5") (pin "CATHODE") (pinfunction "C_CATHODE") (pintype "passive"))
      (node (ref "LED_9_6") (pin "CATHODE") (pinfunction "C_CATHODE") (pintype "passive"))
      (node (ref "LED_9_7") (pin "CATHODE") (pinfunction "C_CATHODE") (pintype "passive"))
      (node (ref "LED_9_8") (pin "CATHODE") (pinfunction "C_CATHODE") (pintype "passive"))
      (node (ref "U$1") (pin "6") (pinfunction "(PCINT7/ICP/OC0B/ADC7)PA7_6") (pintype "bidirectional"))
    )
    (net (code "11") (name "/P10") (class "Default")
      (node (ref "J1") (pin "4") (pinfunction "4_4") (pintype "passive"))
      (node (ref "LED_0_10") (pin "ANODE") (pinfunction "A_ANODE") (pintype "passive"))
      (node (ref "LED_10_0") (pin "CATHODE") (pinfunction "C_CATHODE") (pintype "passive"))
      (node (ref "LED_10_1") (pin "CATHODE") (pinfunction "C_CATHODE") (pintype "passive"))
      (node (ref "LED_10_2") (pin "CATHODE") (pinfunction "C_CATHODE") (pintype "passive"))
      (node (ref "LED_10_3") (pin "CATHODE") (pinfunction "C_CATHODE") (pintype "passive"))
      (node (ref "LED_10_4") (pin "CATHODE") (pinfunction "C_CATHODE") (pintype "passive"))
      (node (ref "LED_10_5") (pin "CATHODE") (pinfunction "C_CATHODE") (pintype "passive"))
      (node (ref "LED_10_6") (pin "CATHODE") (pinfunction "C_CATHODE") (pintype "passive"))
      (node (ref "LED_10_7") (pin "CATHODE") (pinfunction "C_CATHODE") (pintype "passive"))
      (node (ref "LED_10_8") (pin "CATHODE") (pinfunction "C_CATHODE") (pintype "passive"))
      (node (ref "LED_10_9") (pin "CATHODE") (pinfunction "C_CATHODE") (pintype "passive"))
      (node (ref "LED_1_10") (pin "ANODE") (pinfunction "A_ANODE") (pintype "passive"))
      (node (ref "LED_2_10") (pin "ANODE") (pinfunction "A_ANODE") (pintype "passive"))
      (node (ref "LED_3_10") (pin "ANODE") (pinfunction "A_ANODE") (pintype "passive"))
      (node (ref "LED_4_10") (pin "ANODE") (pinfunction "A_ANODE") (pintype "passive"))
      (node (ref "LED_5_10") (pin "ANODE") (pinfunction "A_ANODE") (pintype "passive"))
      (node (ref "LED_6_10") (pin "ANODE") (pinfunction "A_ANODE") (pintype "passive"))
      (node (ref "LED_7_10") (pin "ANODE") (pinfunction "A_ANODE") (pintype "passive"))
      (node (ref "LED_8_10") (pin "ANODE") (pinfunction "A_ANODE") (pintype "passive"))
      (node (ref "LED_9_10") (pin "ANODE") (pinfunction "A_ANODE") (pintype "passive"))
      (node (ref "U$1") (pin "7") (pinfunction "(PCINT6/OC1A/SDA/MOSI/ADC6)PA6_7") (pintype "bidirectional"))
    )
    (net (code "12") (name "/RST") (class "Default")
      (node (ref "J1") (pin "5") (pinfunction "5_5") (pintype "passive"))
      (node (ref "S1") (pin "3") (pinfunction "3_3") (pintype "passive"))
      (node (ref "S1") (pin "4") (pinfunction "4_4") (pintype "passive"))
      (node (ref "U$1") (pin "4") (pinfunction "(PCINT11/~{RESET/DW})PB3_4") (pintype "bidirectional"))
    )
    (net (code "13") (name "5V") (class "Default")
      (node (ref "J1") (pin "2") (pinfunction "2_2") (pintype "passive"))
      (node (ref "U$1") (pin "1") (pinfunction "VCC_1") (pintype "bidirectional"))
      (node (ref "U$2") (pin "+1") (pinfunction "+_+1") (pintype "passive"))
      (node (ref "U$2") (pin "+2") (pinfunction "+1_+2") (pintype "passive"))
    )
    (net (code "14") (name "GND") (class "Default")
      (node (ref "J1") (pin "6") (pinfunction "6_6") (pintype "passive"))
      (node (ref "S1") (pin "1") (pinfunction "1_1") (pintype "passive"))
      (node (ref "S1") (pin "2") (pinfunction "2_2") (pintype "passive"))
      (node (ref "U$1") (pin "14") (pinfunction "GND_14") (pintype "bidirectional"))
      (node (ref "U$2") (pin "-") (pinfunction "-_-") (pintype "passive"))
    )
  )
)
